# RAK3162_Pinout.net
KiCad netlist of a schematic drawn in Altium Designer
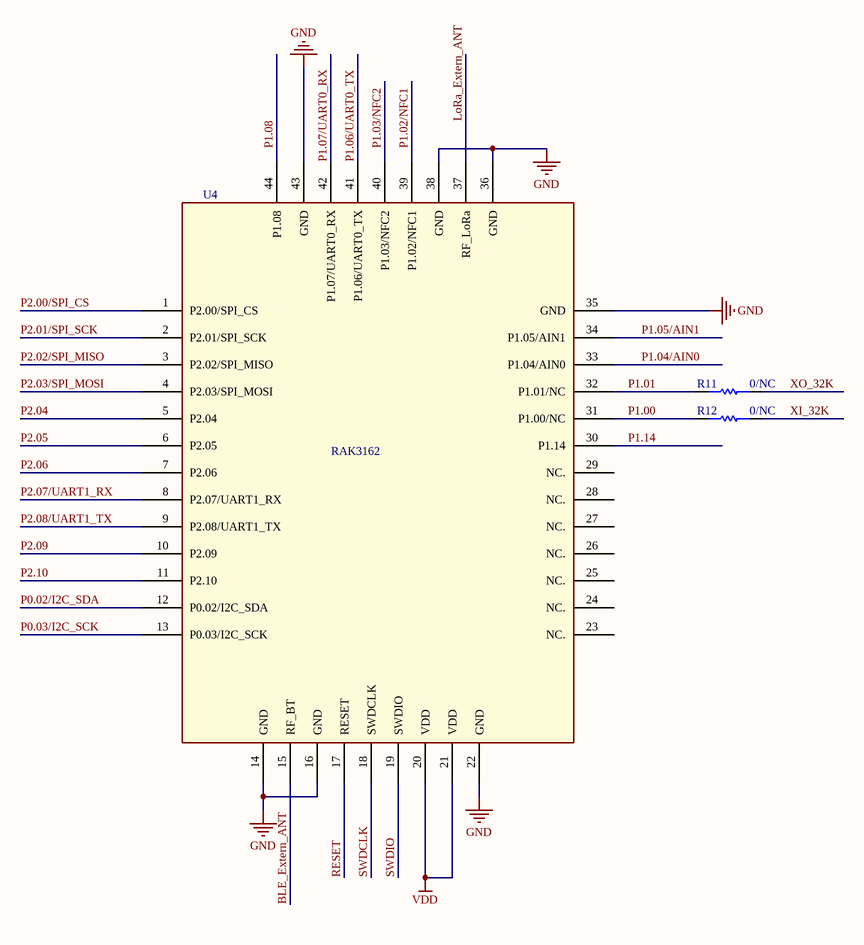
[diagram p0: RAK3162_Pinout.SchDoc]

(export (version "E")
  (design (tool "Eeschema 10.0.6"))
  (components
    (comp (ref "R11")
      (value "0/NC")
      (footprint "sr0201")
      (description "Resistor-0Ω-0.5A-50mΩMAX-0201")
      (fields (field (name "MANUFACTURER") "YAGEO") (field (name "PART NUMBER") "RC0201JR-070RL"))
      (libsource (lib "RAK_Database_Lib_2022") (part "RESISTOR"))
    )
    (comp (ref "R12")
      (value "0/NC")
      (footprint "sr0201")
      (description "Resistor-0Ω-0.5A-50mΩMAX-0201")
      (fields (field (name "MANUFACTURER") "YAGEO") (field (name "PART NUMBER") "RC0201JR-070RL"))
      (libsource (lib "RAK_Database_Lib_2022") (part "RESISTOR"))
    )
    (comp (ref "U4")
      (value "RAK3162")
      (footprint "RAK4630_PINOUT")
      (libsource (lib "RAK_Symbol_Library") (part "RAK3162"))
    )
  )
  (nets
    (net (code "1") (name "/BLE_Extern_ANT") (class "Default")
      (node (ref "U4") (pin "15") (pinfunction "RF_BT_15") (pintype "passive"))
    )
    (net (code "2") (name "/LoRa_Extern_ANT") (class "Default")
      (node (ref "U4") (pin "37") (pinfunction "RF_LoRa_37") (pintype "passive"))
    )
    (net (code "3") (name "/P0.02{slash}I2C_SDA") (class "Default")
      (node (ref "U4") (pin "12") (pinfunction "P0.02/I2C_SDA_12") (pintype "passive"))
    )
    (net (code "4") (name "/P0.03{slash}I2C_SCK") (class "Default")
      (node (ref "U4") (pin "13") (pinfunction "P0.03/I2C_SCK_13") (pintype "passive"))
    )
    (net (code "5") (name "/P1.00") (class "Default")
      (node (ref "R12") (pin "2") (pinfunction "2_2") (pintype "passive"))
      (node (ref "U4") (pin "31") (pinfunction "P1.00/NC_31") (pintype "passive"))
    )
    (net (code "6") (name "/P1.01") (class "Default")
      (node (ref "R11") (pin "2") (pinfunction "2_2") (pintype "passive"))
      (node (ref "U4") (pin "32") (pinfunction "P1.01/NC_32") (pintype "passive"))
    )
    (net (code "7") (name "/P1.02{slash}NFC1") (class "Default")
      (node (ref "U4") (pin "39") (pinfunction "P1.02/NFC1_39") (pintype "passive"))
    )
    (net (code "8") (name "/P1.03{slash}NFC2") (class "Default")
      (node (ref "U4") (pin "40") (pinfunction "P1.03/NFC2_40") (pintype "passive"))
    )
    (net (code "9") (name "/P1.04{slash}AIN0") (class "Default")
      (node (ref "U4") (pin "33") (pinfunction "P1.04/AIN0_33") (pintype "passive"))
    )
    (net (code "10") (name "/P1.05{slash}AIN1") (class "Default")
      (node (ref "U4") (pin "34") (pinfunction "P1.05/AIN1_34") (pintype "passive"))
    )
    (net (code "11") (name "/P1.06{slash}UART0_TX") (class "Default")
      (node (ref "U4") (pin "41") (pinfunction "P1.06/UART0_TX_41") (pintype "passive"))
    )
    (net (code "12") (name "/P1.07{slash}UART0_RX") (class "Default")
      (node (ref "U4") (pin "42") (pinfunction "P1.07/UART0_RX_42") (pintype "passive"))
    )
    (net (code "13") (name "/P1.08") (class "Default")
      (node (ref "U4") (pin "44") (pinfunction "P1.08_44") (pintype "passive"))
    )
    (net (code "14") (name "/P1.14") (class "Default")
      (node (ref "U4") (pin "30") (pinfunction "P1.14_30") (pintype "passive"))
    )
    (net (code "15") (name "/P2.00{slash}SPI_CS") (class "Default")
      (node (ref "U4") (pin "1") (pinfunction "P2.00/SPI_CS_1") (pintype "passive"))
    )
    (net (code "16") (name "/P2.01{slash}SPI_SCK") (class "Default")
      (node (ref "U4") (pin "2") (pinfunction "P2.01/SPI_SCK_2") (pintype "passive"))
    )
    (net (code "17") (name "/P2.02{slash}SPI_MISO") (class "Default")
      (node (ref "U4") (pin "3") (pinfunction "P2.02/SPI_MISO_3") (pintype "passive"))
    )
    (net (code "18") (name "/P2.03{slash}SPI_MOSI") (class "Default")
      (node (ref "U4") (pin "4") (pinfunction "P2.03/SPI_MOSI_4") (pintype "passive"))
    )
    (net (code "19") (name "/P2.04") (class "Default")
      (node (ref "U4") (pin "5") (pinfunction "P2.04_5") (pintype "passive"))
    )
    (net (code "20") (name "/P2.05") (class "Default")
      (node (ref "U4") (pin "6") (pinfunction "P2.05_6") (pintype "passive"))
    )
    (net (code "21") (name "/P2.06") (class "Default")
      (node (ref "U4") (pin "7") (pinfunction "P2.06_7") (pintype "passive"))
    )
    (net (code "22") (name "/P2.07{slash}UART1_RX") (class "Default")
      (node (ref "U4") (pin "8") (pinfunction "P2.07/UART1_RX_8") (pintype "passive"))
    )
    (net (code "23") (name "/P2.08{slash}UART1_TX") (class "Default")
      (node (ref "U4") (pin "9") (pinfunction "P2.08/UART1_TX_9") (pintype "passive"))
    )
    (net (code "24") (name "/P2.09") (class "Default")
      (node (ref "U4") (pin "10") (pinfunction "P2.09_10") (pintype "passive"))
    )
    (net (code "25") (name "/P2.10") (class "Default")
      (node (ref "U4") (pin "11") (pinfunction "P2.10_11") (pintype "passive"))
    )
    (net (code "26") (name "/RESET") (class "Default")
      (node (ref "U4") (pin "17") (pinfunction "RESET_17") (pintype "passive"))
    )
    (net (code "27") (name "/SWDCLK") (class "Default")
      (node (ref "U4") (pin "18") (pinfunction "SWDCLK_18") (pintype "passive"))
    )
    (net (code "28") (name "/SWDIO") (class "Default")
      (node (ref "U4") (pin "19") (pinfunction "SWDIO_19") (pintype "passive"))
    )
    (net (code "29") (name "/XI_32K") (class "Default")
      (node (ref "R12") (pin "1") (pinfunction "1_1") (pintype "passive"))
    )
    (net (code "30") (name "/XO_32K") (class "Default")
      (node (ref "R11") (pin "1") (pinfunction "1_1") (pintype "passive"))
    )
    (net (code "31") (name "GND") (class "Default")
      (node (ref "U4") (pin "14") (pinfunction "GND_14") (pintype "power_in"))
      (node (ref "U4") (pin "16") (pinfunction "GND_16") (pintype "power_in"))
      (node (ref "U4") (pin "22") (pinfunction "GND_22") (pintype "power_in"))
      (node (ref "U4") (pin "35") (pinfunction "GND_35") (pintype "power_in"))
      (node (ref "U4") (pin "36") (pinfunction "GND_36") (pintype "power_in"))
      (node (ref "U4") (pin "38") (pinfunction "GND_38") (pintype "power_in"))
      (node (ref "U4") (pin "43") (pinfunction "GND_43") (pintype "passive"))
    )
    (net (code "32") (name "VDD") (class "Default")
      (node (ref "U4") (pin "20") (pinfunction "VDD_20") (pintype "power_in"))
      (node (ref "U4") (pin "21") (pinfunction "VDD_21") (pintype "power_in"))
    )
    (net (code "33") (name "unconnected-(U4-NC.-Pad23)") (class "Default")
      (node (ref "U4") (pin "23") (pinfunction "NC._23") (pintype "passive"))
    )
    (net (code "34") (name "unconnected-(U4-NC.-Pad24)") (class "Default")
      (node (ref "U4") (pin "24") (pinfunction "NC._24") (pintype "passive"))
    )
    (net (code "35") (name "unconnected-(U4-NC.-Pad25)") (class "Default")
      (node (ref "U4") (pin "25") (pinfunction "NC._25") (pintype "passive"))
    )
    (net (code "36") (name "unconnected-(U4-NC.-Pad26)") (class "Default")
      (node (ref "U4") (pin "26") (pinfunction "NC._26") (pintype "passive"))
    )
    (net (code "37") (name "unconnected-(U4-NC.-Pad27)") (class "Default")
      (node (ref "U4") (pin "27") (pinfunction "NC._27") (pintype "passive"))
    )
    (net (code "38") (name "unconnected-(U4-NC.-Pad28)") (class "Default")
      (node (ref "U4") (pin "28") (pinfunction "NC._28") (pintype "passive"))
    )
    (net (code "39") (name "unconnected-(U4-NC.-Pad29)") (class "Default")
      (node (ref "U4") (pin "29") (pinfunction "NC._29") (pintype "passive"))
    )
  )
)
